# Sheet1.net
KiCad netlist of a schematic drawn in Altium Designer
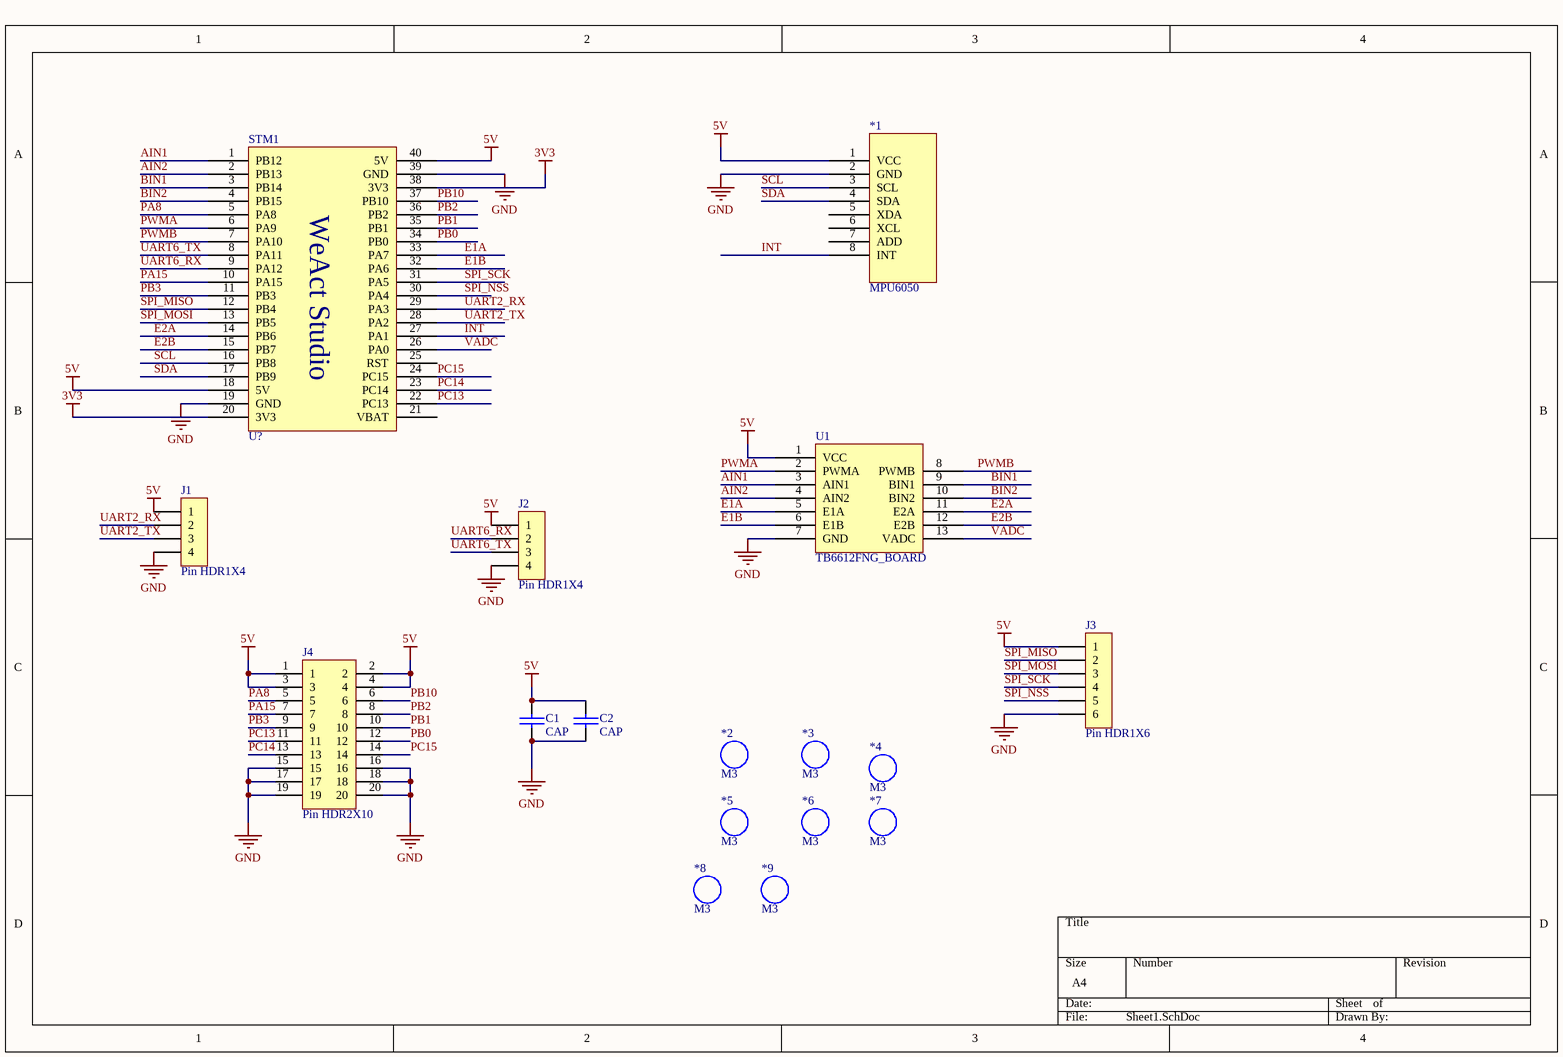
[diagram p0: Sheet1.SchDoc]

(export (version "E")
  (design (tool "Eeschema 10.0.6"))
  (components
    (comp (ref "*1") (value "MPU6050") (footprint "MPU6050") (libsource (lib "0.02-模块") (part "MPU6050")))
    (comp (ref "*2")
      (value "M3")
      (footprint "M3 125X300")
      (description "铜柱孔")
      (fields (field (name "版权归属") "封装库来自淘宝 ID：黄晶宝石"))
      (libsource (lib "9.09-固定柱") (part "M3"))
    )
    (comp (ref "*3")
      (value "M3")
      (footprint "M3 125X300")
      (description "铜柱孔")
      (fields (field (name "版权归属") "封装库来自淘宝 ID：黄晶宝石"))
      (libsource (lib "9.09-固定柱") (part "M3"))
    )
    (comp (ref "*4")
      (value "M3")
      (footprint "M3 125X300")
      (description "铜柱孔")
      (fields (field (name "版权归属") "封装库来自淘宝 ID：黄晶宝石"))
      (libsource (lib "9.09-固定柱") (part "M3"))
    )
    (comp (ref "*5")
      (value "M3")
      (footprint "M3 125X300")
      (description "铜柱孔")
      (fields (field (name "版权归属") "封装库来自淘宝 ID：黄晶宝石"))
      (libsource (lib "9.09-固定柱") (part "M3"))
    )
    (comp (ref "*6")
      (value "M3")
      (footprint "M3 125X300")
      (description "铜柱孔")
      (fields (field (name "版权归属") "封装库来自淘宝 ID：黄晶宝石"))
      (libsource (lib "9.09-固定柱") (part "M3"))
    )
    (comp (ref "*7")
      (value "M3")
      (footprint "M3 125X300")
      (description "铜柱孔")
      (fields (field (name "版权归属") "封装库来自淘宝 ID：黄晶宝石"))
      (libsource (lib "9.09-固定柱") (part "M3"))
    )
    (comp (ref "*8")
      (value "M3")
      (footprint "M3 125X300")
      (description "铜柱孔")
      (fields (field (name "版权归属") "封装库来自淘宝 ID：黄晶宝石"))
      (libsource (lib "9.09-固定柱") (part "M3"))
    )
    (comp (ref "*9")
      (value "M3")
      (footprint "M3 125X300")
      (description "铜柱孔")
      (fields (field (name "版权归属") "封装库来自淘宝 ID：黄晶宝石"))
      (libsource (lib "9.09-固定柱") (part "M3"))
    )
    (comp (ref "C1")
      (value "CAP")
      (footprint "RAD-0.2")
      (description "无极性电容")
      (libsource (lib "1.00-阻容感") (part "CAP"))
    )
    (comp (ref "C2")
      (value "CAP")
      (footprint "RAD-0.2")
      (description "无极性电容")
      (libsource (lib "1.00-阻容感") (part "CAP"))
    )
    (comp (ref "J1")
      (value "Pin HDR1X4")
      (footprint "Pin HDR1X4/2.54mm-S")
      (libsource (lib "8.01-排针") (part "Pin HDR1X4"))
    )
    (comp (ref "J2")
      (value "Pin HDR1X4")
      (footprint "Pin HDR1X4/2.54mm-S")
      (libsource (lib "8.01-排针") (part "Pin HDR1X4"))
    )
    (comp (ref "J3")
      (value "Pin HDR1X6")
      (footprint "Pin HDR1X6/2.54mm-S")
      (libsource (lib "8.01-排针") (part "Pin HDR1X6"))
    )
    (comp (ref "J4")
      (value "Pin HDR2X10")
      (footprint "Pin HDR2X10/2.54mm-S")
      (libsource (lib "8.01-排针") (part "Pin HDR2X10"))
    )
    (comp (ref "STM1")
      (value "U?")
      (footprint "STM32F4x1CxU6 WeActStudio")
      (description "STM32F4x1CxU6")
      (libsource (lib "0.02-模块") (part "STM32F4x1CxU6 WeActStudio"))
    )
    (comp (ref "U1")
      (value "TB6612FNG_BOARD")
      (footprint "TB6612FNG_BOARD")
      (description "tb6612电机驱动器，包含编码器")
      (libsource (lib "0.02-模块") (part "TB6612FNG_BOARD"))
    )
  )
  (nets
    (net (code "1") (name "/AIN1") (class "Default")
      (node (ref "STM1") (pin "1") (pinfunction "PB12_1") (pintype "passive"))
      (node (ref "U1") (pin "3") (pinfunction "AIN1_3") (pintype "passive"))
    )
    (net (code "2") (name "/AIN2") (class "Default")
      (node (ref "STM1") (pin "2") (pinfunction "PB13_2") (pintype "passive"))
      (node (ref "U1") (pin "4") (pinfunction "AIN2_4") (pintype "passive"))
    )
    (net (code "3") (name "/BIN1") (class "Default")
      (node (ref "STM1") (pin "3") (pinfunction "PB14_3") (pintype "passive"))
      (node (ref "U1") (pin "9") (pinfunction "BIN1_9") (pintype "passive"))
    )
    (net (code "4") (name "/BIN2") (class "Default")
      (node (ref "STM1") (pin "4") (pinfunction "PB15_4") (pintype "passive"))
      (node (ref "U1") (pin "10") (pinfunction "BIN2_10") (pintype "passive"))
    )
    (net (code "5") (name "/E1A") (class "Default")
      (node (ref "STM1") (pin "33") (pinfunction "PA7_33") (pintype "passive"))
      (node (ref "U1") (pin "5") (pinfunction "E1A_5") (pintype "passive"))
    )
    (net (code "6") (name "/E1B") (class "Default")
      (node (ref "STM1") (pin "32") (pinfunction "PA6_32") (pintype "passive"))
      (node (ref "U1") (pin "6") (pinfunction "E1B_6") (pintype "passive"))
    )
    (net (code "7") (name "/E2A") (class "Default")
      (node (ref "STM1") (pin "14") (pinfunction "PB6_14") (pintype "passive"))
      (node (ref "U1") (pin "11") (pinfunction "E2A_11") (pintype "passive"))
    )
    (net (code "8") (name "/E2B") (class "Default")
      (node (ref "STM1") (pin "15") (pinfunction "PB7_15") (pintype "passive"))
      (node (ref "U1") (pin "12") (pinfunction "E2B_12") (pintype "passive"))
    )
    (net (code "9") (name "/INT") (class "Default")
      (node (ref "*1") (pin "8") (pinfunction "INT_8") (pintype "passive"))
      (node (ref "STM1") (pin "27") (pinfunction "PA1_27") (pintype "passive"))
    )
    (net (code "10") (name "/PA8") (class "Default")
      (node (ref "J4") (pin "5") (pinfunction "5_5") (pintype "passive"))
      (node (ref "STM1") (pin "5") (pinfunction "PA8_5") (pintype "passive"))
    )
    (net (code "11") (name "/PA15") (class "Default")
      (node (ref "J4") (pin "7") (pinfunction "7_7") (pintype "passive"))
      (node (ref "STM1") (pin "10") (pinfunction "PA15_10") (pintype "passive"))
    )
    (net (code "12") (name "/PB0") (class "Default")
      (node (ref "J4") (pin "12") (pinfunction "12_12") (pintype "passive"))
      (node (ref "STM1") (pin "34") (pinfunction "PB0_34") (pintype "passive"))
    )
    (net (code "13") (name "/PB1") (class "Default")
      (node (ref "J4") (pin "10") (pinfunction "10_10") (pintype "passive"))
      (node (ref "STM1") (pin "35") (pinfunction "PB1_35") (pintype "passive"))
    )
    (net (code "14") (name "/PB2") (class "Default")
      (node (ref "J4") (pin "8") (pinfunction "8_8") (pintype "passive"))
      (node (ref "STM1") (pin "36") (pinfunction "PB2_36") (pintype "passive"))
    )
    (net (code "15") (name "/PB3") (class "Default")
      (node (ref "J4") (pin "9") (pinfunction "9_9") (pintype "passive"))
      (node (ref "STM1") (pin "11") (pinfunction "PB3_11") (pintype "passive"))
    )
    (net (code "16") (name "/PB10") (class "Default")
      (node (ref "J4") (pin "6") (pinfunction "6_6") (pintype "passive"))
      (node (ref "STM1") (pin "37") (pinfunction "PB10_37") (pintype "passive"))
    )
    (net (code "17") (name "/PC13") (class "Default")
      (node (ref "J4") (pin "11") (pinfunction "11_11") (pintype "passive"))
      (node (ref "STM1") (pin "22") (pinfunction "PC13_22") (pintype "passive"))
    )
    (net (code "18") (name "/PC14") (class "Default")
      (node (ref "J4") (pin "13") (pinfunction "13_13") (pintype "passive"))
      (node (ref "STM1") (pin "23") (pinfunction "PC14_23") (pintype "passive"))
    )
    (net (code "19") (name "/PC15") (class "Default")
      (node (ref "J4") (pin "14") (pinfunction "14_14") (pintype "passive"))
      (node (ref "STM1") (pin "24") (pinfunction "PC15_24") (pintype "passive"))
    )
    (net (code "20") (name "/PWMA") (class "Default")
      (node (ref "STM1") (pin "6") (pinfunction "PA9_6") (pintype "passive"))
      (node (ref "U1") (pin "2") (pinfunction "PWMA_2") (pintype "passive"))
    )
    (net (code "21") (name "/PWMB") (class "Default")
      (node (ref "STM1") (pin "7") (pinfunction "PA10_7") (pintype "passive"))
      (node (ref "U1") (pin "8") (pinfunction "PWMB_8") (pintype "passive"))
    )
    (net (code "22") (name "/SCL") (class "Default")
      (node (ref "*1") (pin "3") (pinfunction "SCL_3") (pintype "passive"))
      (node (ref "STM1") (pin "16") (pinfunction "PB8_16") (pintype "passive"))
    )
    (net (code "23") (name "/SDA") (class "Default")
      (node (ref "*1") (pin "4") (pinfunction "SDA_4") (pintype "passive"))
      (node (ref "STM1") (pin "17") (pinfunction "PB9_17") (pintype "passive"))
    )
    (net (code "24") (name "/SPI_MISO") (class "Default")
      (node (ref "J3") (pin "2") (pinfunction "2_2") (pintype "passive"))
      (node (ref "STM1") (pin "12") (pinfunction "PB4_12") (pintype "passive"))
    )
    (net (code "25") (name "/SPI_MOSI") (class "Default")
      (node (ref "J3") (pin "3") (pinfunction "3_3") (pintype "passive"))
      (node (ref "STM1") (pin "13") (pinfunction "PB5_13") (pintype "passive"))
    )
    (net (code "26") (name "/SPI_NSS") (class "Default")
      (node (ref "J3") (pin "5") (pinfunction "5_5") (pintype "passive"))
      (node (ref "STM1") (pin "30") (pinfunction "PA4_30") (pintype "passive"))
    )
    (net (code "27") (name "/SPI_SCK") (class "Default")
      (node (ref "J3") (pin "4") (pinfunction "4_4") (pintype "passive"))
      (node (ref "STM1") (pin "31") (pinfunction "PA5_31") (pintype "passive"))
    )
    (net (code "28") (name "/UART2_RX") (class "Default")
      (node (ref "J1") (pin "2") (pinfunction "2_2") (pintype "passive"))
      (node (ref "STM1") (pin "29") (pinfunction "PA3_29") (pintype "passive"))
    )
    (net (code "29") (name "/UART2_TX") (class "Default")
      (node (ref "J1") (pin "3") (pinfunction "3_3") (pintype "passive"))
      (node (ref "STM1") (pin "28") (pinfunction "PA2_28") (pintype "passive"))
    )
    (net (code "30") (name "/UART6_RX") (class "Default")
      (node (ref "J2") (pin "2") (pinfunction "2_2") (pintype "passive"))
      (node (ref "STM1") (pin "9") (pinfunction "PA12_9") (pintype "passive"))
    )
    (net (code "31") (name "/UART6_TX") (class "Default")
      (node (ref "J2") (pin "3") (pinfunction "3_3") (pintype "passive"))
      (node (ref "STM1") (pin "8") (pinfunction "PA11_8") (pintype "passive"))
    )
    (net (code "32") (name "/VADC") (class "Default")
      (node (ref "STM1") (pin "26") (pinfunction "PA0_26") (pintype "passive"))
      (node (ref "U1") (pin "13") (pinfunction "VADC_13") (pintype "passive"))
    )
    (net (code "33") (name "3V3") (class "Default")
      (node (ref "STM1") (pin "20") (pinfunction "3V3_20") (pintype "passive"))
      (node (ref "STM1") (pin "38") (pinfunction "3V3_38") (pintype "passive"))
    )
    (net (code "34") (name "5V") (class "Default")
      (node (ref "*1") (pin "1") (pinfunction "VCC_1") (pintype "power_in"))
      (node (ref "C1") (pin "2") (pinfunction "2_2") (pintype "passive"))
      (node (ref "C2") (pin "2") (pinfunction "2_2") (pintype "passive"))
      (node (ref "J1") (pin "1") (pinfunction "1_1") (pintype "passive"))
      (node (ref "J2") (pin "1") (pinfunction "1_1") (pintype "passive"))
      (node (ref "J3") (pin "1") (pinfunction "1_1") (pintype "passive"))
      (node (ref "J4") (pin "1") (pinfunction "1_1") (pintype "passive"))
      (node (ref "J4") (pin "2") (pinfunction "2_2") (pintype "passive"))
      (node (ref "J4") (pin "3") (pinfunction "3_3") (pintype "passive"))
      (node (ref "J4") (pin "4") (pinfunction "4_4") (pintype "passive"))
      (node (ref "STM1") (pin "18") (pinfunction "5V_18") (pintype "passive"))
      (node (ref "STM1") (pin "40") (pinfunction "5V_40") (pintype "passive"))
      (node (ref "U1") (pin "1") (pinfunction "VCC_1") (pintype "passive"))
    )
    (net (code "35") (name "GND") (class "Default")
      (node (ref "*1") (pin "2") (pinfunction "GND_2") (pintype "power_in"))
      (node (ref "C1") (pin "1") (pinfunction "1_1") (pintype "passive"))
      (node (ref "C2") (pin "1") (pinfunction "1_1") (pintype "passive"))
      (node (ref "J1") (pin "4") (pinfunction "4_4") (pintype "passive"))
      (node (ref "J2") (pin "4") (pinfunction "4_4") (pintype "passive"))
      (node (ref "J3") (pin "6") (pinfunction "6_6") (pintype "passive"))
      (node (ref "J4") (pin "15") (pinfunction "15_15") (pintype "passive"))
      (node (ref "J4") (pin "16") (pinfunction "16_16") (pintype "passive"))
      (node (ref "J4") (pin "17") (pinfunction "17_17") (pintype "passive"))
      (node (ref "J4") (pin "18") (pinfunction "18_18") (pintype "passive"))
      (node (ref "J4") (pin "19") (pinfunction "19_19") (pintype "passive"))
      (node (ref "J4") (pin "20") (pinfunction "20_20") (pintype "passive"))
      (node (ref "STM1") (pin "19") (pinfunction "GND_19") (pintype "passive"))
      (node (ref "STM1") (pin "39") (pinfunction "GND_39") (pintype "passive"))
      (node (ref "U1") (pin "7") (pinfunction "GND_7") (pintype "passive"))
    )
    (net (code "36") (name "unconnected-(*1-ADD-Pad7)") (class "Default")
      (node (ref "*1") (pin "7") (pinfunction "ADD_7") (pintype "passive"))
    )
    (net (code "37") (name "unconnected-(*1-XCL-Pad6)") (class "Default")
      (node (ref "*1") (pin "6") (pinfunction "XCL_6") (pintype "passive"))
    )
    (net (code "38") (name "unconnected-(*1-XDA-Pad5)") (class "Default")
      (node (ref "*1") (pin "5") (pinfunction "XDA_5") (pintype "passive"))
    )
    (net (code "39") (name "unconnected-(STM1-RST-Pad25)") (class "Default")
      (node (ref "STM1") (pin "25") (pinfunction "RST_25") (pintype "passive"))
    )
    (net (code "40") (name "unconnected-(STM1-VBAT-Pad21)") (class "Default")
      (node (ref "STM1") (pin "21") (pinfunction "VBAT_21") (pintype "passive"))
    )
  )
)
